# Current_Detection_Connectors.net
KiCad netlist of a schematic drawn in Altium Designer
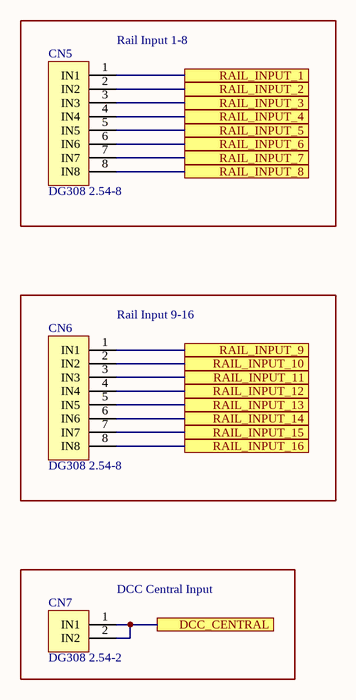
[diagram p0: Current_Detection_Connectors.SchDoc]

(export (version "E")
  (design (tool "Eeschema 10.0.6"))
  (components
    (comp (ref "CN5")
      (value "DG308 2.54-8")
      (footprint "DG308 2.54-8")
      (libsource (lib "Schematic_Library_S88N") (part "8_Pin_Screw_Connector"))
    )
    (comp (ref "CN6")
      (value "DG308 2.54-8")
      (footprint "DG308 2.54-8")
      (libsource (lib "Schematic_Library_S88N") (part "8_Pin_Screw_Connector"))
    )
    (comp (ref "CN7")
      (value "DG308 2.54-2")
      (footprint "DG308 2.54-2")
      (libsource (lib "Schematic_Library_S88N") (part "2_Pin_Screw_Connector"))
    )
  )
  (nets
    (net (code "1") (name "/DCC_CENTRAL") (class "Default")
      (node (ref "CN7") (pin "1") (pinfunction "IN1_1") (pintype "passive"))
      (node (ref "CN7") (pin "2") (pinfunction "IN2_2") (pintype "passive"))
    )
    (net (code "2") (name "/RAIL_INPUT_1") (class "Default")
      (node (ref "CN5") (pin "1") (pinfunction "IN1_1") (pintype "passive"))
    )
    (net (code "3") (name "/RAIL_INPUT_2") (class "Default")
      (node (ref "CN5") (pin "2") (pinfunction "IN2_2") (pintype "passive"))
    )
    (net (code "4") (name "/RAIL_INPUT_3") (class "Default")
      (node (ref "CN5") (pin "3") (pinfunction "IN3_3") (pintype "passive"))
    )
    (net (code "5") (name "/RAIL_INPUT_4") (class "Default")
      (node (ref "CN5") (pin "4") (pinfunction "IN4_4") (pintype "passive"))
    )
    (net (code "6") (name "/RAIL_INPUT_5") (class "Default")
      (node (ref "CN5") (pin "5") (pinfunction "IN5_5") (pintype "passive"))
    )
    (net (code "7") (name "/RAIL_INPUT_6") (class "Default")
      (node (ref "CN5") (pin "6") (pinfunction "IN6_6") (pintype "passive"))
    )
    (net (code "8") (name "/RAIL_INPUT_7") (class "Default")
      (node (ref "CN5") (pin "7") (pinfunction "IN7_7") (pintype "passive"))
    )
    (net (code "9") (name "/RAIL_INPUT_8") (class "Default")
      (node (ref "CN5") (pin "8") (pinfunction "IN8_8") (pintype "passive"))
    )
    (net (code "10") (name "/RAIL_INPUT_9") (class "Default")
      (node (ref "CN6") (pin "1") (pinfunction "IN1_1") (pintype "passive"))
    )
    (net (code "11") (name "/RAIL_INPUT_10") (class "Default")
      (node (ref "CN6") (pin "2") (pinfunction "IN2_2") (pintype "passive"))
    )
    (net (code "12") (name "/RAIL_INPUT_11") (class "Default")
      (node (ref "CN6") (pin "3") (pinfunction "IN3_3") (pintype "passive"))
    )
    (net (code "13") (name "/RAIL_INPUT_12") (class "Default")
      (node (ref "CN6") (pin "4") (pinfunction "IN4_4") (pintype "passive"))
    )
    (net (code "14") (name "/RAIL_INPUT_13") (class "Default")
      (node (ref "CN6") (pin "5") (pinfunction "IN5_5") (pintype "passive"))
    )
    (net (code "15") (name "/RAIL_INPUT_14") (class "Default")
      (node (ref "CN6") (pin "6") (pinfunction "IN6_6") (pintype "passive"))
    )
    (net (code "16") (name "/RAIL_INPUT_15") (class "Default")
      (node (ref "CN6") (pin "7") (pinfunction "IN7_7") (pintype "passive"))
    )
    (net (code "17") (name "/RAIL_INPUT_16") (class "Default")
      (node (ref "CN6") (pin "8") (pinfunction "IN8_8") (pintype "passive"))
    )
  )
)
